# SH3-FTDI.net
KiCad netlist of a schematic drawn in Altium Designer
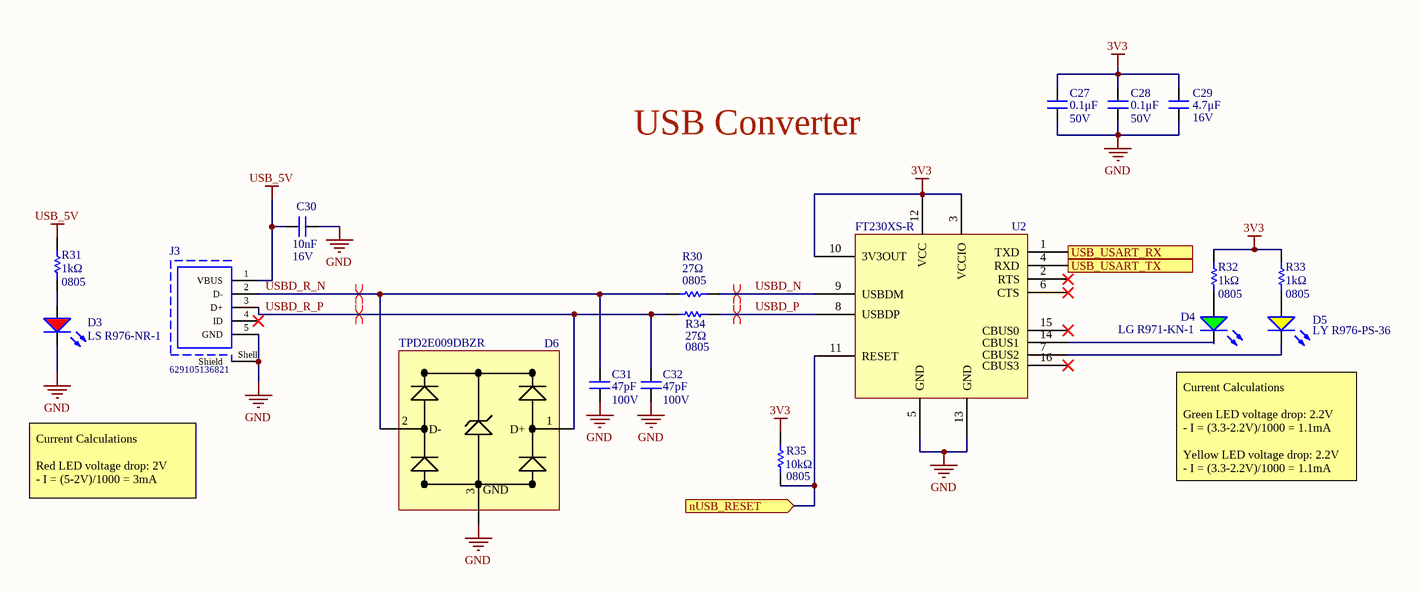
[diagram p0: SH3-FTDI.SchDoc]

(export (version "E")
  (design (tool "Eeschema 10.0.6"))
  (components
    (comp (ref "C27")
      (value "0.1μF")
      (footprint "CAPC2012X140N")
      (description "CAP CER 0.1UF 50V X7R 0805")
      (fields (field (name "TOLERANCE") "10%") (field (name "VOLTAGE RATING") "50V"))
      (libsource (lib "*") (part "CAP_0.1uF_50V_0805"))
    )
    (comp (ref "C28")
      (value "0.1μF")
      (footprint "CAPC2012X140N")
      (description "CAP CER 0.1UF 50V X7R 0805")
      (fields (field (name "TOLERANCE") "10%") (field (name "VOLTAGE RATING") "50V"))
      (libsource (lib "*") (part "CAP_0.1uF_50V_0805"))
    )
    (comp (ref "C29")
      (value "4.7μF")
      (footprint "CAPC2012X140N")
      (description "CAP CER 4.7UF 16V X5R 0805")
      (fields (field (name "TOLERANCE") "10%") (field (name "VOLTAGE RATING") "16V"))
      (libsource (lib "*") (part "CAP_4.7uF_16V_0805"))
    )
    (comp (ref "C30")
      (value "~")
      (footprint "CAPC2012X140N")
      (description "CAP CER 10000PF 16V X7R 0805")
      (fields
        (field (name "TOLERANCE") "10%")
        (field (name "CAPACITANCE") "10nF")
        (field (name "VOLTAGE RATING") "16V")
      )
      (libsource (lib "*") (part "CAP_10nF_16V_0805"))
    )
    (comp (ref "C31")
      (value "~")
      (footprint "CAPC2012X140N")
      (description "CAP CER 47PF 100V NPO 0805")
      (fields
        (field (name "TOLERANCE") "5%")
        (field (name "CAPACITANCE") "47pF")
        (field (name "VOLTAGE RATING") "100V")
      )
      (libsource (lib "*") (part "CAP_47pF_100V_0805"))
    )
    (comp (ref "C32")
      (value "~")
      (footprint "CAPC2012X140N")
      (description "CAP CER 47PF 100V NPO 0805")
      (fields
        (field (name "TOLERANCE") "5%")
        (field (name "CAPACITANCE") "47pF")
        (field (name "VOLTAGE RATING") "100V")
      )
      (libsource (lib "*") (part "CAP_47pF_100V_0805"))
    )
    (comp (ref "D3")
      (value "LS R976-NR-1")
      (footprint "LED_0805_LINE")
      (description "LED RED DIFFUSED 0805 SMD")
      (libsource (lib "UWRT_Schematic_Library_2020") (part "DIO_LED_R"))
    )
    (comp (ref "D4")
      (value "LG R971-KN-1")
      (footprint "LED_0805_LINE")
      (description "LED GREEN DIFFUSED 0805 SMD")
      (libsource (lib "UWRT_Schematic_Library_2020") (part "DIO_LED_G"))
    )
    (comp (ref "D5")
      (value "LY R976-PS-36")
      (footprint "LED_0805_LINE")
      (description "LED YELLOW DIFFUSED 0805 SMD")
      (libsource (lib "UWRT_Schematic_Library_2020") (part "DIO_LED_Y"))
    )
    (comp (ref "D6")
      (value "TVS_DIODE_USB_5.5V")
      (footprint "SOT23-3")
      (description "ESD Suppressor Diode Arrays 8KV 3-Pin SOT-23 T/R")
      (fields
        (field (name "MANUFACTURER") "Texas Instruments")
        (field (name "MANUFACTURER PART NUMBER") "TPD2E009DBZR")
      )
      (libsource (lib "UWRT_Schematic_Library_2020") (part "TVS_DIODE_USB_5.5V"))
    )
    (comp (ref "J3")
      (value "629105136821")
      (footprint "629105136821")
      (description "Micro USB 2.0 Type B Receptacle WR-COM, Horizontal, SMT, with Pads and Pegs")
      (fields (field (name "MANUFACTURER") "Wurth Elektronik") (field (name "PUBLISHER") "WurthElektronik"))
      (libsource (lib "Altium Content Vault") (part "WE-USB-5-1SHLD"))
    )
    (comp (ref "R30")
      (value "RES_27Ω_0805")
      (footprint "RESC2012X60N")
      (description "RES SMD 27 OHM 1% 1/8W 0805")
      (fields
        (field (name "TOLERANCE") "1%")
        (field (name "CASE/PACKAGE") "0805")
        (field (name "RESISTANCE") "27Ω")
      )
      (libsource (lib "UWRT_Schematic_Library_2020") (part "RES_27Ω_0805"))
    )
    (comp (ref "R31")
      (value "1kΩ")
      (footprint "RESC2012X60N")
      (description "RES SMD 1K OHM 1% 1/8W 0805")
      (fields (field (name "TOLERANCE") "1%") (field (name "CASE CODE (IMPERIAL)") "0805"))
      (libsource (lib "UWRT_Schematic_Library_2020") (part "RES_1kΩ_0805"))
    )
    (comp (ref "R32")
      (value "1kΩ")
      (footprint "RESC2012X60N")
      (description "RES SMD 1K OHM 1% 1/8W 0805")
      (fields (field (name "TOLERANCE") "1%") (field (name "CASE CODE (IMPERIAL)") "0805"))
      (libsource (lib "UWRT_Schematic_Library_2020") (part "RES_1kΩ_0805"))
    )
    (comp (ref "R33")
      (value "1kΩ")
      (footprint "RESC2012X60N")
      (description "RES SMD 1K OHM 1% 1/8W 0805")
      (fields (field (name "TOLERANCE") "1%") (field (name "CASE CODE (IMPERIAL)") "0805"))
      (libsource (lib "UWRT_Schematic_Library_2020") (part "RES_1kΩ_0805"))
    )
    (comp (ref "R34")
      (value "RES_27Ω_0805")
      (footprint "RESC2012X60N")
      (description "RES SMD 27 OHM 1% 1/8W 0805")
      (fields
        (field (name "TOLERANCE") "1%")
        (field (name "CASE/PACKAGE") "0805")
        (field (name "RESISTANCE") "27Ω")
      )
      (libsource (lib "UWRT_Schematic_Library_2020") (part "RES_27Ω_0805"))
    )
    (comp (ref "R35")
      (value "10kΩ")
      (footprint "RESC2012X60N")
      (description "RES SMD 10K OHM 1% 1/8W 0805")
      (fields
        (field (name "TOLERANCE") "1%")
        (field (name "CASE CODE (IMPERIAL)") "0805")
        (field (name "Comment") "RES_10kΩ_0805")
      )
      (libsource (lib "UWRT_Schematic_Library_2020") (part "RES_10kΩ_0805"))
    )
    (comp (ref "U2")
      (value "IC_USB_TRANSCEIVER")
      (footprint "SSOP16-0.635-5X4MM")
      (fields (field (name "MANUFACTURER PART NUMBER 1") "FT230XS-R"))
      (libsource (lib "UWRT_Schematic_Library_2020") (part "IC_USB_TRANSCEIVER"))
    )
  )
  (nets
    (net (code "1") (name "/USBD_N") (class "Default")
      (node (ref "R30") (pin "2") (pinfunction "2_2") (pintype "passive"))
      (node (ref "U2") (pin "9") (pinfunction "USBDM_9") (pintype "passive"))
    )
    (net (code "2") (name "/USBD_P") (class "Default")
      (node (ref "R34") (pin "2") (pinfunction "2_2") (pintype "passive"))
      (node (ref "U2") (pin "8") (pinfunction "USBDP_8") (pintype "passive"))
    )
    (net (code "3") (name "/USBD_R_N") (class "Default")
      (node (ref "C31") (pin "1") (pinfunction "1_1") (pintype "passive"))
      (node (ref "D6") (pin "2") (pinfunction "D-_2") (pintype "passive"))
      (node (ref "J3") (pin "2") (pinfunction "D-_2") (pintype "passive"))
      (node (ref "R30") (pin "1") (pinfunction "1_1") (pintype "passive"))
    )
    (net (code "4") (name "/USBD_R_P") (class "Default")
      (node (ref "C32") (pin "1") (pinfunction "1_1") (pintype "passive"))
      (node (ref "D6") (pin "1") (pinfunction "D+_1") (pintype "passive"))
      (node (ref "J3") (pin "3") (pinfunction "D+_3") (pintype "passive"))
      (node (ref "R34") (pin "1") (pinfunction "1_1") (pintype "passive"))
    )
    (net (code "5") (name "/USB_USART_RX") (class "Default")
      (node (ref "U2") (pin "1") (pinfunction "TXD_1") (pintype "passive"))
    )
    (net (code "6") (name "/USB_USART_TX") (class "Default")
      (node (ref "U2") (pin "4") (pinfunction "RXD_4") (pintype "passive"))
    )
    (net (code "7") (name "/nUSB_RESET") (class "Default")
      (node (ref "R35") (pin "1") (pinfunction "1_1") (pintype "passive"))
      (node (ref "U2") (pin "11") (pinfunction "RESET_11") (pintype "passive"))
    )
    (net (code "8") (name "3V3") (class "Default")
      (node (ref "C27") (pin "2") (pinfunction "2_2") (pintype "passive"))
      (node (ref "C28") (pin "2") (pinfunction "2_2") (pintype "passive"))
      (node (ref "C29") (pin "2") (pinfunction "2_2") (pintype "passive"))
      (node (ref "R32") (pin "2") (pinfunction "2_2") (pintype "passive"))
      (node (ref "R33") (pin "2") (pinfunction "2_2") (pintype "passive"))
      (node (ref "R35") (pin "2") (pinfunction "2_2") (pintype "passive"))
      (node (ref "U2") (pin "10") (pinfunction "3V3OUT_10") (pintype "passive"))
      (node (ref "U2") (pin "12") (pinfunction "VCC_12") (pintype "passive"))
      (node (ref "U2") (pin "3") (pinfunction "VCCIO_3") (pintype "passive"))
    )
    (net (code "9") (name "GND") (class "Default")
      (node (ref "C27") (pin "1") (pinfunction "1_1") (pintype "passive"))
      (node (ref "C28") (pin "1") (pinfunction "1_1") (pintype "passive"))
      (node (ref "C29") (pin "1") (pinfunction "1_1") (pintype "passive"))
      (node (ref "C30") (pin "2") (pinfunction "2_2") (pintype "passive"))
      (node (ref "C31") (pin "2") (pinfunction "2_2") (pintype "passive"))
      (node (ref "C32") (pin "2") (pinfunction "2_2") (pintype "passive"))
      (node (ref "D3") (pin "2") (pinfunction "K_2") (pintype "passive"))
      (node (ref "D6") (pin "3") (pinfunction "GND_3") (pintype "passive"))
      (node (ref "J3") (pin "5") (pinfunction "GND_5") (pintype "passive"))
      (node (ref "J3") (pin "Shell") (pinfunction "Shield_Shell") (pintype "passive"))
      (node (ref "U2") (pin "13") (pinfunction "GND_13") (pintype "passive"))
      (node (ref "U2") (pin "5") (pinfunction "GND_5") (pintype "passive"))
    )
    (net (code "10") (name "Net-(D3-A)") (class "Default")
      (node (ref "D3") (pin "1") (pinfunction "A_1") (pintype "passive"))
      (node (ref "R31") (pin "1") (pinfunction "1_1") (pintype "passive"))
    )
    (net (code "11") (name "Net-(D4-A)") (class "Default")
      (node (ref "D4") (pin "1") (pinfunction "A_1") (pintype "passive"))
      (node (ref "R32") (pin "1") (pinfunction "1_1") (pintype "passive"))
    )
    (net (code "12") (name "Net-(D4-K)") (class "Default")
      (node (ref "D4") (pin "2") (pinfunction "K_2") (pintype "passive"))
      (node (ref "U2") (pin "14") (pinfunction "CBUS1_14") (pintype "passive"))
    )
    (net (code "13") (name "Net-(D5-A)") (class "Default")
      (node (ref "D5") (pin "1") (pinfunction "A_1") (pintype "passive"))
      (node (ref "R33") (pin "1") (pinfunction "1_1") (pintype "passive"))
    )
    (net (code "14") (name "Net-(D5-K)") (class "Default")
      (node (ref "D5") (pin "2") (pinfunction "K_2") (pintype "passive"))
      (node (ref "U2") (pin "7") (pinfunction "CBUS2_7") (pintype "passive"))
    )
    (net (code "15") (name "USB_5V") (class "Default")
      (node (ref "C30") (pin "1") (pinfunction "1_1") (pintype "passive"))
      (node (ref "J3") (pin "1") (pinfunction "VBUS_1") (pintype "passive"))
      (node (ref "R31") (pin "2") (pinfunction "2_2") (pintype "passive"))
    )
    (net (code "16") (name "unconnected-(J3-ID-Pad4)") (class "Default")
      (node (ref "J3") (pin "4") (pinfunction "ID_4") (pintype "passive+no_connect"))
    )
    (net (code "17") (name "unconnected-(U2-CBUS0-Pad15)") (class "Default")
      (node (ref "U2") (pin "15") (pinfunction "CBUS0_15") (pintype "passive+no_connect"))
    )
    (net (code "18") (name "unconnected-(U2-CBUS3-Pad16)") (class "Default")
      (node (ref "U2") (pin "16") (pinfunction "CBUS3_16") (pintype "passive+no_connect"))
    )
    (net (code "19") (name "unconnected-(U2-CTS-Pad6)") (class "Default")
      (node (ref "U2") (pin "6") (pinfunction "CTS_6") (pintype "passive+no_connect"))
    )
    (net (code "20") (name "unconnected-(U2-RTS-Pad2)") (class "Default")
      (node (ref "U2") (pin "2") (pinfunction "RTS_2") (pintype "passive+no_connect"))
    )
  )
)
